# Top.net
KiCad netlist of a schematic drawn in Altium Designer
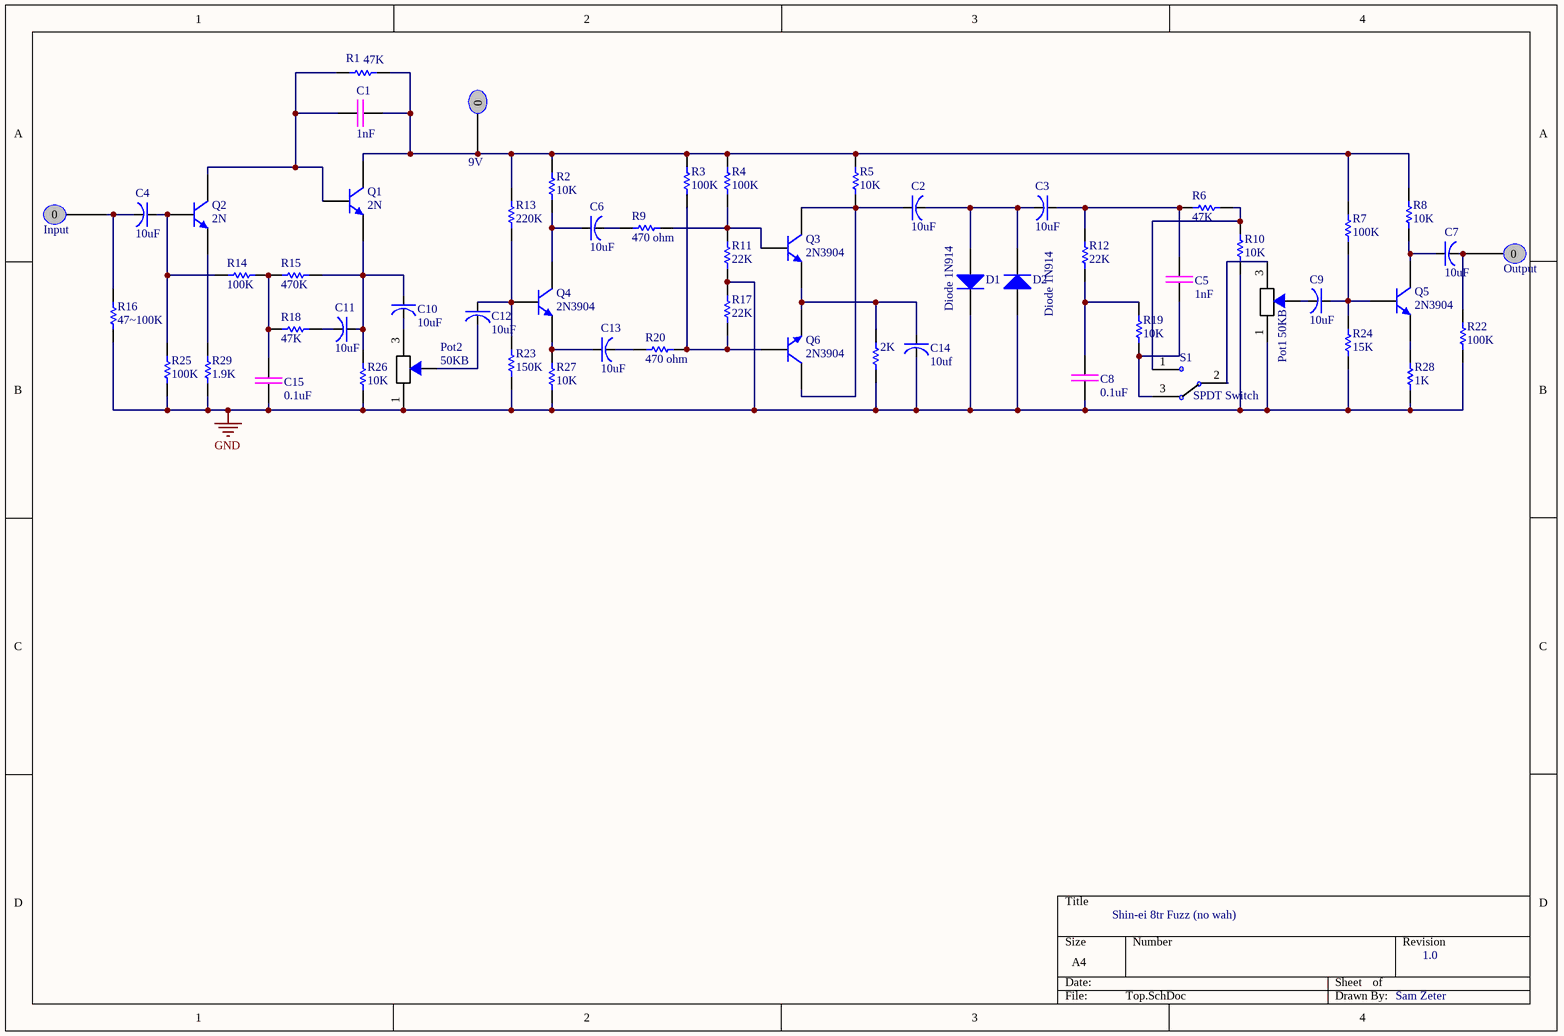
[diagram p0: Top.SchDoc]

(export (version "E")
  (design (tool "Eeschema 10.0.6"))
  (components
    (comp (ref "2K")
      (value "~")
      (footprint "RES Axial 0.5 Tayda")
      (description "Radial 1/4 Watt Tayda")
      (fields (field (name "PUBLISHER") "Altium Limited"))
      (libsource (lib "Zeter") (part "Res 0.5"))
    )
    (comp (ref "9V") (value "General purpose pad") (footprint "Pin") (libsource (lib "Zeter") (part "Pad")))
    (comp (ref "C1")
      (value "1nF")
      (footprint "Cap Green 3.5mm")
      (description "3.5mm spaced leads for green caps")
      (libsource (lib "Zeter") (part "Cap Green 3.5mm"))
    )
    (comp (ref "C2")
      (value "10uF")
      (footprint "Capacitor Electrolytic 2mm")
      (description "2mm Lead Spaced Electro Cap")
      (libsource (lib "Zeter") (part "Cap Elec 2mm"))
    )
    (comp (ref "C3")
      (value "10uF")
      (footprint "Capacitor Electrolytic 2mm")
      (description "2mm Lead Spaced Electro Cap")
      (libsource (lib "Zeter") (part "Cap Elec 2mm"))
    )
    (comp (ref "C4")
      (value "10uF")
      (footprint "Capacitor Electrolytic 2mm")
      (description "2mm Lead Spaced Electro Cap")
      (libsource (lib "Zeter") (part "Cap Elec 2mm"))
    )
    (comp (ref "C5")
      (value "1nF")
      (footprint "Cap Green 3.5mm")
      (description "3.5mm spaced leads for green caps")
      (libsource (lib "Zeter") (part "Cap Green 3.5mm"))
    )
    (comp (ref "C6")
      (value "10uF")
      (footprint "Capacitor Electrolytic 2mm")
      (description "2mm Lead Spaced Electro Cap")
      (libsource (lib "Zeter") (part "Cap Elec 2mm"))
    )
    (comp (ref "C7")
      (value "10uF")
      (footprint "Capacitor Electrolytic 2mm")
      (description "2mm Lead Spaced Electro Cap")
      (libsource (lib "Zeter") (part "Cap Elec 2mm"))
    )
    (comp (ref "C8")
      (value "0.1uF")
      (footprint "Cap Green 5.4mm")
      (description "5.4mm spaced Tayda green caps")
      (libsource (lib "Zeter") (part "Cap Green 5.4mm spaced Tayda green caps"))
    )
    (comp (ref "C9")
      (value "10uF")
      (footprint "Capacitor Electrolytic 2mm")
      (description "2mm Lead Spaced Electro Cap")
      (libsource (lib "Zeter") (part "Cap Elec 2mm"))
    )
    (comp (ref "C10")
      (value "10uF")
      (footprint "Capacitor Electrolytic 2mm")
      (description "2mm Lead Spaced Electro Cap")
      (libsource (lib "Zeter") (part "Cap Elec 2mm"))
    )
    (comp (ref "C11")
      (value "10uF")
      (footprint "Capacitor Electrolytic 2mm")
      (description "2mm Lead Spaced Electro Cap")
      (libsource (lib "Zeter") (part "Cap Elec 2mm"))
    )
    (comp (ref "C12")
      (value "10uF")
      (footprint "Capacitor Electrolytic 2mm")
      (description "2mm Lead Spaced Electro Cap")
      (libsource (lib "Zeter") (part "Cap Elec 2mm"))
    )
    (comp (ref "C13")
      (value "10uF")
      (footprint "Capacitor Electrolytic 2mm")
      (description "2mm Lead Spaced Electro Cap")
      (libsource (lib "Zeter") (part "Cap Elec 2mm"))
    )
    (comp (ref "C14")
      (value "10uf")
      (footprint "Capacitor Electrolytic 2mm")
      (description "2mm Lead Spaced Electro Cap")
      (libsource (lib "Zeter") (part "Cap Elec 2mm"))
    )
    (comp (ref "C15")
      (value "0.1uF")
      (footprint "Cap Green 5.4mm")
      (description "5.4mm spaced Tayda green caps")
      (libsource (lib "Zeter") (part "Cap Green 5.4mm spaced Tayda green caps"))
    )
    (comp (ref "D1")
      (value "Diode 1N914")
      (footprint "DO-35")
      (description "High Conductance Fast Diode")
      (fields (field (name "PUBLISHER") "Altium Limited"))
      (libsource (lib "Miscellaneous Devices") (part "Diode 1N914"))
    )
    (comp (ref "D2")
      (value "Diode 1N914")
      (footprint "DO-35")
      (description "High Conductance Fast Diode")
      (fields (field (name "PUBLISHER") "Altium Limited"))
      (libsource (lib "Miscellaneous Devices") (part "Diode 1N914"))
    )
    (comp (ref "Input")
      (value "General purpose pad")
      (footprint "Pin")
      (libsource (lib "Zeter") (part "Pad"))
    )
    (comp (ref "Output")
      (value "General purpose pad")
      (footprint "Pin")
      (libsource (lib "Zeter") (part "Pad"))
    )
    (comp (ref "Pot1")
      (value "50KB")
      (footprint "Potentiometer")
      (description "My Own")
      (libsource (lib "Zeter") (part "Potentiometer"))
    )
    (comp (ref "Pot2")
      (value "50KB")
      (footprint "Potentiometer")
      (description "My Own")
      (libsource (lib "Zeter") (part "Potentiometer"))
    )
    (comp (ref "Q1")
      (value "2N")
      (footprint "NPN Transistor Wide")
      (description "NPN  Larger Leg Spacing")
      (libsource (lib "Zeter") (part "NPN Transistor"))
    )
    (comp (ref "Q2")
      (value "2N")
      (footprint "NPN Transistor Wide")
      (description "NPN  Larger Leg Spacing")
      (libsource (lib "Zeter") (part "NPN Transistor"))
    )
    (comp (ref "Q3")
      (value "2N3904")
      (footprint "NPN Transistor Wide")
      (description "NPN  Larger Leg Spacing")
      (libsource (lib "Zeter") (part "NPN Transistor"))
    )
    (comp (ref "Q4")
      (value "2N3904")
      (footprint "NPN Transistor Wide")
      (description "NPN  Larger Leg Spacing")
      (libsource (lib "Zeter") (part "NPN Transistor"))
    )
    (comp (ref "Q5")
      (value "2N3904")
      (footprint "NPN Transistor Wide")
      (description "NPN  Larger Leg Spacing")
      (libsource (lib "Zeter") (part "NPN Transistor"))
    )
    (comp (ref "Q6")
      (value "2N3904")
      (footprint "NPN Transistor Wide")
      (description "NPN  Larger Leg Spacing")
      (libsource (lib "Zeter") (part "NPN Transistor"))
    )
    (comp (ref "R1")
      (value "47K")
      (footprint "RES Axial 0.5 Tayda")
      (description "Radial 1/4 Watt Tayda")
      (fields (field (name "PUBLISHER") "Altium Limited"))
      (libsource (lib "Zeter") (part "Res 0.5"))
    )
    (comp (ref "R2")
      (value "10K")
      (footprint "RES Axial 0.5 Tayda")
      (description "Radial 1/4 Watt Tayda")
      (fields (field (name "PUBLISHER") "Altium Limited"))
      (libsource (lib "Zeter") (part "Res 0.5"))
    )
    (comp (ref "R3")
      (value "100K")
      (footprint "RES Axial 0.5 Tayda")
      (description "Radial 1/4 Watt Tayda")
      (fields (field (name "PUBLISHER") "Altium Limited"))
      (libsource (lib "Zeter") (part "Res 0.5"))
    )
    (comp (ref "R4")
      (value "100K")
      (footprint "RES Axial 0.5 Tayda")
      (description "Radial 1/4 Watt Tayda")
      (fields (field (name "PUBLISHER") "Altium Limited"))
      (libsource (lib "Zeter") (part "Res 0.5"))
    )
    (comp (ref "R5")
      (value "10K")
      (footprint "RES Axial 0.5 Tayda")
      (description "Radial 1/4 Watt Tayda")
      (fields (field (name "PUBLISHER") "Altium Limited"))
      (libsource (lib "Zeter") (part "Res 0.5"))
    )
    (comp (ref "R6")
      (value "47K")
      (footprint "RES Axial 0.5 Tayda")
      (description "Radial 1/4 Watt Tayda")
      (fields (field (name "PUBLISHER") "Altium Limited"))
      (libsource (lib "Zeter") (part "Res 0.5"))
    )
    (comp (ref "R7")
      (value "100K")
      (footprint "RES Axial 0.5 Tayda")
      (description "Radial 1/4 Watt Tayda")
      (fields (field (name "PUBLISHER") "Altium Limited"))
      (libsource (lib "Zeter") (part "Res 0.5"))
    )
    (comp (ref "R8")
      (value "10K")
      (footprint "RES Axial 0.5 Tayda")
      (description "Radial 1/4 Watt Tayda")
      (fields (field (name "PUBLISHER") "Altium Limited"))
      (libsource (lib "Zeter") (part "Res 0.5"))
    )
    (comp (ref "R9")
      (value "470 ohm")
      (footprint "RES Axial 0.5 Tayda")
      (description "Radial 1/4 Watt Tayda")
      (fields (field (name "PUBLISHER") "Altium Limited"))
      (libsource (lib "Zeter") (part "Res 0.5"))
    )
    (comp (ref "R10")
      (value "10K")
      (footprint "RES Axial 0.5 Tayda")
      (description "Radial 1/4 Watt Tayda")
      (fields (field (name "PUBLISHER") "Altium Limited"))
      (libsource (lib "Zeter") (part "Res 0.5"))
    )
    (comp (ref "R11")
      (value "22K")
      (footprint "RES Axial 0.5 Tayda")
      (description "Radial 1/4 Watt Tayda")
      (fields (field (name "PUBLISHER") "Altium Limited"))
      (libsource (lib "Zeter") (part "Res 0.5"))
    )
    (comp (ref "R12")
      (value "22K")
      (footprint "RES Axial 0.5 Tayda")
      (description "Radial 1/4 Watt Tayda")
      (fields (field (name "PUBLISHER") "Altium Limited"))
      (libsource (lib "Zeter") (part "Res 0.5"))
    )
    (comp (ref "R13")
      (value "220K")
      (footprint "RES Axial 0.5 Tayda")
      (description "Radial 1/4 Watt Tayda")
      (fields (field (name "PUBLISHER") "Altium Limited"))
      (libsource (lib "Zeter") (part "Res 0.5"))
    )
    (comp (ref "R14")
      (value "100K")
      (footprint "RES Axial 0.5 Tayda")
      (description "Radial 1/4 Watt Tayda")
      (fields (field (name "PUBLISHER") "Altium Limited"))
      (libsource (lib "Zeter") (part "Res 0.5"))
    )
    (comp (ref "R15")
      (value "470K")
      (footprint "RES Axial 0.5 Tayda")
      (description "Radial 1/4 Watt Tayda")
      (fields (field (name "PUBLISHER") "Altium Limited"))
      (libsource (lib "Zeter") (part "Res 0.5"))
    )
    (comp (ref "R16")
      (value "47~100K")
      (footprint "RES Axial 0.5 Tayda")
      (description "Radial 1/4 Watt Tayda")
      (fields (field (name "PUBLISHER") "Altium Limited"))
      (libsource (lib "Zeter") (part "Res 0.5"))
    )
    (comp (ref "R17")
      (value "22K")
      (footprint "RES Axial 0.5 Tayda")
      (description "Radial 1/4 Watt Tayda")
      (fields (field (name "PUBLISHER") "Altium Limited"))
      (libsource (lib "Zeter") (part "Res 0.5"))
    )
    (comp (ref "R18")
      (value "47K")
      (footprint "RES Axial 0.5 Tayda")
      (description "Radial 1/4 Watt Tayda")
      (fields (field (name "PUBLISHER") "Altium Limited"))
      (libsource (lib "Zeter") (part "Res 0.5"))
    )
    (comp (ref "R19")
      (value "10K")
      (footprint "RES Axial 0.5 Tayda")
      (description "Radial 1/4 Watt Tayda")
      (fields (field (name "PUBLISHER") "Altium Limited"))
      (libsource (lib "Zeter") (part "Res 0.5"))
    )
    (comp (ref "R20")
      (value "470 ohm")
      (footprint "RES Axial 0.5 Tayda")
      (description "Radial 1/4 Watt Tayda")
      (fields (field (name "PUBLISHER") "Altium Limited"))
      (libsource (lib "Zeter") (part "Res 0.5"))
    )
    (comp (ref "R22")
      (value "100K")
      (footprint "RES Axial 0.5 Tayda")
      (description "Radial 1/4 Watt Tayda")
      (fields (field (name "PUBLISHER") "Altium Limited"))
      (libsource (lib "Zeter") (part "Res 0.5"))
    )
    (comp (ref "R23")
      (value "150K")
      (footprint "RES Axial 0.5 Tayda")
      (description "Radial 1/4 Watt Tayda")
      (fields (field (name "PUBLISHER") "Altium Limited"))
      (libsource (lib "Zeter") (part "Res 0.5"))
    )
    (comp (ref "R24")
      (value "15K")
      (footprint "RES Axial 0.5 Tayda")
      (description "Radial 1/4 Watt Tayda")
      (fields (field (name "PUBLISHER") "Altium Limited"))
      (libsource (lib "Zeter") (part "Res 0.5"))
    )
    (comp (ref "R25")
      (value "100K")
      (footprint "RES Axial 0.5 Tayda")
      (description "Radial 1/4 Watt Tayda")
      (fields (field (name "PUBLISHER") "Altium Limited"))
      (libsource (lib "Zeter") (part "Res 0.5"))
    )
    (comp (ref "R26")
      (value "10K")
      (footprint "RES Axial 0.5 Tayda")
      (description "Radial 1/4 Watt Tayda")
      (fields (field (name "PUBLISHER") "Altium Limited"))
      (libsource (lib "Zeter") (part "Res 0.5"))
    )
    (comp (ref "R27")
      (value "10K")
      (footprint "RES Axial 0.5 Tayda")
      (description "Radial 1/4 Watt Tayda")
      (fields (field (name "PUBLISHER") "Altium Limited"))
      (libsource (lib "Zeter") (part "Res 0.5"))
    )
    (comp (ref "R28")
      (value "1K")
      (footprint "RES Axial 0.5 Tayda")
      (description "Radial 1/4 Watt Tayda")
      (fields (field (name "PUBLISHER") "Altium Limited"))
      (libsource (lib "Zeter") (part "Res 0.5"))
    )
    (comp (ref "R29")
      (value "1.9K")
      (footprint "RES Axial 0.5 Tayda")
      (description "Radial 1/4 Watt Tayda")
      (fields (field (name "PUBLISHER") "Altium Limited"))
      (libsource (lib "Zeter") (part "Res 0.5"))
    )
    (comp (ref "S1")
      (value "SPDT Switch")
      (footprint "SPDT Switch")
      (libsource (lib "Zeter") (part "SPDT Switch"))
    )
  )
  (nets
    (net (code "1") (name "GND") (class "Default")
      (node (ref "2K") (pin "1") (pinfunction "1_1") (pintype "passive"))
      (node (ref "C14") (pin "2") (pinfunction "2_2") (pintype "passive"))
      (node (ref "C15") (pin "1") (pinfunction "1_1") (pintype "passive"))
      (node (ref "C8") (pin "1") (pinfunction "1_1") (pintype "passive"))
      (node (ref "D1") (pin "2") (pinfunction "K_2") (pintype "passive"))
      (node (ref "D2") (pin "1") (pinfunction "A_1") (pintype "passive"))
      (node (ref "Pot1") (pin "1") (pinfunction "1_1") (pintype "passive"))
      (node (ref "Pot2") (pin "1") (pinfunction "1_1") (pintype "passive"))
      (node (ref "R10") (pin "1") (pinfunction "1_1") (pintype "passive"))
      (node (ref "R11") (pin "1") (pinfunction "1_1") (pintype "passive"))
      (node (ref "R16") (pin "1") (pinfunction "1_1") (pintype "passive"))
      (node (ref "R17") (pin "2") (pinfunction "2_2") (pintype "passive"))
      (node (ref "R22") (pin "1") (pinfunction "1_1") (pintype "passive"))
      (node (ref "R23") (pin "1") (pinfunction "1_1") (pintype "passive"))
      (node (ref "R24") (pin "1") (pinfunction "1_1") (pintype "passive"))
      (node (ref "R25") (pin "1") (pinfunction "1_1") (pintype "passive"))
      (node (ref "R26") (pin "1") (pinfunction "1_1") (pintype "passive"))
      (node (ref "R27") (pin "1") (pinfunction "1_1") (pintype "passive"))
      (node (ref "R28") (pin "1") (pinfunction "1_1") (pintype "passive"))
      (node (ref "R29") (pin "1") (pinfunction "1_1") (pintype "passive"))
    )
    (net (code "2") (name "Net-(C3-Pad1)") (class "Default")
      (node (ref "C3") (pin "1") (pinfunction "1_1") (pintype "passive"))
      (node (ref "C5") (pin "2") (pinfunction "2_2") (pintype "passive"))
      (node (ref "R12") (pin "2") (pinfunction "2_2") (pintype "passive"))
      (node (ref "R6") (pin "2") (pinfunction "2_2") (pintype "passive"))
    )
    (net (code "3") (name "Net-(C4-Pad2)") (class "Default")
      (node (ref "C4") (pin "2") (pinfunction "2_2") (pintype "passive"))
      (node (ref "Input") (pin "0") (pinfunction "0_0") (pintype "passive"))
      (node (ref "R16") (pin "2") (pinfunction "2_2") (pintype "passive"))
    )
    (net (code "4") (name "Net-(C5-Pad1)") (class "Default")
      (node (ref "C5") (pin "1") (pinfunction "1_1") (pintype "passive"))
      (node (ref "R19") (pin "1") (pinfunction "1_1") (pintype "passive"))
      (node (ref "S1") (pin "3") (pinfunction "3_3") (pintype "passive"))
    )
    (net (code "5") (name "Net-(C6-Pad2)") (class "Default")
      (node (ref "C6") (pin "2") (pinfunction "2_2") (pintype "passive"))
      (node (ref "R9") (pin "1") (pinfunction "1_1") (pintype "passive"))
    )
    (net (code "6") (name "Net-(C7-Pad2)") (class "Default")
      (node (ref "C7") (pin "2") (pinfunction "2_2") (pintype "passive"))
      (node (ref "Output") (pin "0") (pinfunction "0_0") (pintype "passive"))
      (node (ref "R22") (pin "2") (pinfunction "2_2") (pintype "passive"))
    )
    (net (code "7") (name "Net-(C8-Pad2)") (class "Default")
      (node (ref "C8") (pin "2") (pinfunction "2_2") (pintype "passive"))
      (node (ref "R12") (pin "1") (pinfunction "1_1") (pintype "passive"))
      (node (ref "R19") (pin "2") (pinfunction "2_2") (pintype "passive"))
    )
    (net (code "8") (name "Net-(C9-Pad2)") (class "Default")
      (node (ref "C9") (pin "2") (pinfunction "2_2") (pintype "passive"))
      (node (ref "Pot1") (pin "2") (pinfunction "2_2") (pintype "passive"))
    )
    (net (code "9") (name "Net-(C10-Pad2)") (class "Default")
      (node (ref "C10") (pin "2") (pinfunction "2_2") (pintype "passive"))
      (node (ref "Pot2") (pin "3") (pinfunction "3_3") (pintype "passive"))
    )
    (net (code "10") (name "Net-(C11-Pad2)") (class "Default")
      (node (ref "C11") (pin "2") (pinfunction "2_2") (pintype "passive"))
      (node (ref "R18") (pin "2") (pinfunction "2_2") (pintype "passive"))
    )
    (net (code "11") (name "Net-(C12-Pad2)") (class "Default")
      (node (ref "C12") (pin "2") (pinfunction "2_2") (pintype "passive"))
      (node (ref "Pot2") (pin "2") (pinfunction "2_2") (pintype "passive"))
    )
    (net (code "12") (name "Net-(C13-Pad2)") (class "Default")
      (node (ref "C13") (pin "2") (pinfunction "2_2") (pintype "passive"))
      (node (ref "R20") (pin "1") (pinfunction "1_1") (pintype "passive"))
    )
    (net (code "13") (name "Net-(C15-Pad2)") (class "Default")
      (node (ref "C15") (pin "2") (pinfunction "2_2") (pintype "passive"))
      (node (ref "R14") (pin "2") (pinfunction "2_2") (pintype "passive"))
      (node (ref "R15") (pin "1") (pinfunction "1_1") (pintype "passive"))
      (node (ref "R18") (pin "1") (pinfunction "1_1") (pintype "passive"))
    )
    (net (code "14") (name "Net-(D1-A)") (class "Default")
      (node (ref "C2") (pin "2") (pinfunction "2_2") (pintype "passive"))
      (node (ref "C3") (pin "2") (pinfunction "2_2") (pintype "passive"))
      (node (ref "D1") (pin "1") (pinfunction "A_1") (pintype "passive"))
      (node (ref "D2") (pin "2") (pinfunction "K_2") (pintype "passive"))
    )
    (net (code "15") (name "Net-(Pot1-Pad3)") (class "Default")
      (node (ref "Pot1") (pin "3") (pinfunction "3_3") (pintype "passive"))
      (node (ref "S1") (pin "2") (pinfunction "2_2") (pintype "passive"))
    )
    (net (code "16") (name "Net-(Q1-B)") (class "Default")
      (node (ref "C1") (pin "1") (pinfunction "1_1") (pintype "passive"))
      (node (ref "Q1") (pin "2") (pinfunction "B_2") (pintype "passive"))
      (node (ref "Q2") (pin "1") (pinfunction "C_1") (pintype "passive"))
      (node (ref "R1") (pin "1") (pinfunction "1_1") (pintype "passive"))
    )
    (net (code "17") (name "Net-(Q1-C)") (class "Default")
      (node (ref "9V") (pin "0") (pinfunction "0_0") (pintype "passive"))
      (node (ref "C1") (pin "2") (pinfunction "2_2") (pintype "passive"))
      (node (ref "Q1") (pin "1") (pinfunction "C_1") (pintype "passive"))
      (node (ref "R1") (pin "2") (pinfunction "2_2") (pintype "passive"))
      (node (ref "R13") (pin "2") (pinfunction "2_2") (pintype "passive"))
      (node (ref "R2") (pin "2") (pinfunction "2_2") (pintype "passive"))
      (node (ref "R3") (pin "2") (pinfunction "2_2") (pintype "passive"))
      (node (ref "R4") (pin "2") (pinfunction "2_2") (pintype "passive"))
      (node (ref "R5") (pin "2") (pinfunction "2_2") (pintype "passive"))
      (node (ref "R7") (pin "2") (pinfunction "2_2") (pintype "passive"))
      (node (ref "R8") (pin "2") (pinfunction "2_2") (pintype "passive"))
    )
    (net (code "18") (name "Net-(Q1-E)") (class "Default")
      (node (ref "C10") (pin "1") (pinfunction "1_1") (pintype "passive"))
      (node (ref "C11") (pin "1") (pinfunction "1_1") (pintype "passive"))
      (node (ref "Q1") (pin "3") (pinfunction "E_3") (pintype "passive"))
      (node (ref "R15") (pin "2") (pinfunction "2_2") (pintype "passive"))
      (node (ref "R26") (pin "2") (pinfunction "2_2") (pintype "passive"))
    )
    (net (code "19") (name "Net-(Q2-B)") (class "Default")
      (node (ref "C4") (pin "1") (pinfunction "1_1") (pintype "passive"))
      (node (ref "Q2") (pin "2") (pinfunction "B_2") (pintype "passive"))
      (node (ref "R14") (pin "1") (pinfunction "1_1") (pintype "passive"))
      (node (ref "R25") (pin "2") (pinfunction "2_2") (pintype "passive"))
    )
    (net (code "20") (name "Net-(Q2-E)") (class "Default")
      (node (ref "Q2") (pin "3") (pinfunction "E_3") (pintype "passive"))
      (node (ref "R29") (pin "2") (pinfunction "2_2") (pintype "passive"))
    )
    (net (code "21") (name "Net-(Q3-B)") (class "Default")
      (node (ref "Q3") (pin "2") (pinfunction "B_2") (pintype "passive"))
      (node (ref "R11") (pin "2") (pinfunction "2_2") (pintype "passive"))
      (node (ref "R4") (pin "1") (pinfunction "1_1") (pintype "passive"))
      (node (ref "R9") (pin "2") (pinfunction "2_2") (pintype "passive"))
    )
    (net (code "22") (name "Net-(Q3-C)") (class "Default")
      (node (ref "C2") (pin "1") (pinfunction "1_1") (pintype "passive"))
      (node (ref "Q3") (pin "1") (pinfunction "C_1") (pintype "passive"))
      (node (ref "Q6") (pin "1") (pinfunction "C_1") (pintype "passive"))
      (node (ref "R5") (pin "1") (pinfunction "1_1") (pintype "passive"))
    )
    (net (code "23") (name "Net-(Q3-E)") (class "Default")
      (node (ref "2K") (pin "2") (pinfunction "2_2") (pintype "passive"))
      (node (ref "C14") (pin "1") (pinfunction "1_1") (pintype "passive"))
      (node (ref "Q3") (pin "3") (pinfunction "E_3") (pintype "passive"))
      (node (ref "Q6") (pin "3") (pinfunction "E_3") (pintype "passive"))
    )
    (net (code "24") (name "Net-(Q4-B)") (class "Default")
      (node (ref "C12") (pin "1") (pinfunction "1_1") (pintype "passive"))
      (node (ref "Q4") (pin "2") (pinfunction "B_2") (pintype "passive"))
      (node (ref "R13") (pin "1") (pinfunction "1_1") (pintype "passive"))
      (node (ref "R23") (pin "2") (pinfunction "2_2") (pintype "passive"))
    )
    (net (code "25") (name "Net-(Q4-C)") (class "Default")
      (node (ref "C6") (pin "1") (pinfunction "1_1") (pintype "passive"))
      (node (ref "Q4") (pin "1") (pinfunction "C_1") (pintype "passive"))
      (node (ref "R2") (pin "1") (pinfunction "1_1") (pintype "passive"))
    )
    (net (code "26") (name "Net-(Q4-E)") (class "Default")
      (node (ref "C13") (pin "1") (pinfunction "1_1") (pintype "passive"))
      (node (ref "Q4") (pin "3") (pinfunction "E_3") (pintype "passive"))
      (node (ref "R27") (pin "2") (pinfunction "2_2") (pintype "passive"))
    )
    (net (code "27") (name "Net-(Q5-B)") (class "Default")
      (node (ref "C9") (pin "1") (pinfunction "1_1") (pintype "passive"))
      (node (ref "Q5") (pin "2") (pinfunction "B_2") (pintype "passive"))
      (node (ref "R24") (pin "2") (pinfunction "2_2") (pintype "passive"))
      (node (ref "R7") (pin "1") (pinfunction "1_1") (pintype "passive"))
    )
    (net (code "28") (name "Net-(Q5-C)") (class "Default")
      (node (ref "C7") (pin "1") (pinfunction "1_1") (pintype "passive"))
      (node (ref "Q5") (pin "1") (pinfunction "C_1") (pintype "passive"))
      (node (ref "R8") (pin "1") (pinfunction "1_1") (pintype "passive"))
    )
    (net (code "29") (name "Net-(Q5-E)") (class "Default")
      (node (ref "Q5") (pin "3") (pinfunction "E_3") (pintype "passive"))
      (node (ref "R28") (pin "2") (pinfunction "2_2") (pintype "passive"))
    )
    (net (code "30") (name "Net-(Q6-B)") (class "Default")
      (node (ref "Q6") (pin "2") (pinfunction "B_2") (pintype "passive"))
      (node (ref "R17") (pin "1") (pinfunction "1_1") (pintype "passive"))
      (node (ref "R20") (pin "2") (pinfunction "2_2") (pintype "passive"))
      (node (ref "R3") (pin "1") (pinfunction "1_1") (pintype "passive"))
    )
    (net (code "31") (name "Net-(R10-Pad2)") (class "Default")
      (node (ref "R10") (pin "2") (pinfunction "2_2") (pintype "passive"))
      (node (ref "R6") (pin "1") (pinfunction "1_1") (pintype "passive"))
      (node (ref "S1") (pin "1") (pinfunction "1_1") (pintype "passive"))
    )
  )
)
